# Single_Matrix.net
KiCad netlist of a schematic drawn in Altium Designer
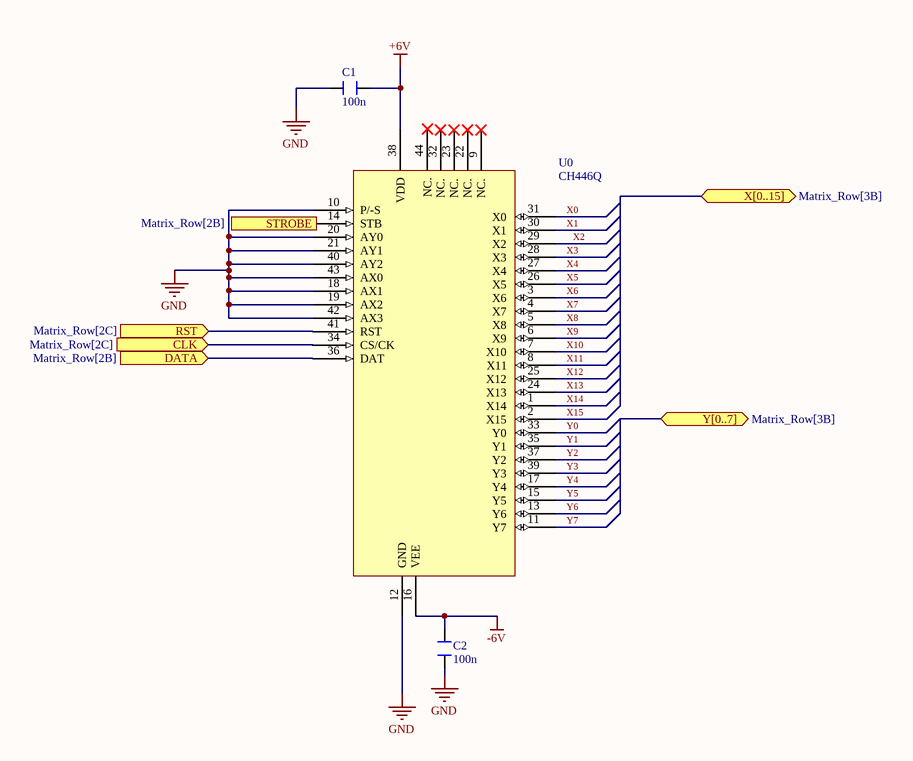
[diagram p0: Single_Matrix.SchDoc]

(export (version "E")
  (design (tool "Eeschema 10.0.6"))
  (components
    (comp (ref "C1")
      (value "100n")
      (footprint "micr_footprints:CL10B104KB8NNNC")
      (description "Capacitor SMD 0603 100n to VDD, VBAT, VDDA, VREF+, VDDUSB, NRST")
      (libsource (lib "unwired_schematic") (part "CL10B104KB8NNNC"))
    )
    (comp (ref "C2")
      (value "100n")
      (footprint "micr_footprints:CL10B104KB8NNNC")
      (description "Capacitor SMD 0603 100n to VDD, VBAT, VDDA, VREF+, VDDUSB, NRST")
      (libsource (lib "unwired_schematic") (part "CL10B104KB8NNNC"))
    )
    (comp (ref "U0")
      (value "CH446Q")
      (footprint "unwired_footprints:LQFP-44_CH446Q")
      (description "Analog Switch Array")
      (libsource (lib "unwired_schematic") (part "CH446Q"))
    )
  )
  (nets
    (net (code "1") (name "+6V") (class "Default")
      (node (ref "C1") (pin "8") (pintype "passive"))
      (node (ref "U0") (pin "38") (pinfunction "VDD_38") (pintype "power_in"))
    )
    (net (code "2") (name "-6V") (class "Default")
      (node (ref "C2") (pin "8") (pintype "passive"))
      (node (ref "U0") (pin "16") (pinfunction "VEE_16") (pintype "power_in"))
    )
    (net (code "3") (name "/CLK") (class "Default")
      (node (ref "U0") (pin "34") (pinfunction "CS/CK_34") (pintype "input"))
    )
    (net (code "4") (name "/DATA") (class "Default")
      (node (ref "U0") (pin "36") (pinfunction "DAT_36") (pintype "input"))
    )
    (net (code "5") (name "/RST") (class "Default")
      (node (ref "U0") (pin "41") (pinfunction "RST_41") (pintype "input"))
    )
    (net (code "7") (name "/X0") (class "Default")
      (node (ref "U0") (pin "31") (pinfunction "X0_31") (pintype "bidirectional"))
    )
    (net (code "8") (name "/X1") (class "Default")
      (node (ref "U0") (pin "30") (pinfunction "X1_30") (pintype "bidirectional"))
    )
    (net (code "9") (name "/X2") (class "Default")
      (node (ref "U0") (pin "29") (pinfunction "X2_29") (pintype "bidirectional"))
    )
    (net (code "10") (name "/X3") (class "Default")
      (node (ref "U0") (pin "28") (pinfunction "X3_28") (pintype "bidirectional"))
    )
    (net (code "11") (name "/X4") (class "Default")
      (node (ref "U0") (pin "27") (pinfunction "X4_27") (pintype "bidirectional"))
    )
    (net (code "12") (name "/X5") (class "Default")
      (node (ref "U0") (pin "26") (pinfunction "X5_26") (pintype "bidirectional"))
    )
    (net (code "13") (name "/X6") (class "Default")
      (node (ref "U0") (pin "3") (pinfunction "X6_3") (pintype "bidirectional"))
    )
    (net (code "14") (name "/X7") (class "Default")
      (node (ref "U0") (pin "4") (pinfunction "X7_4") (pintype "bidirectional"))
    )
    (net (code "15") (name "/X8") (class "Default")
      (node (ref "U0") (pin "5") (pinfunction "X8_5") (pintype "bidirectional"))
    )
    (net (code "16") (name "/X9") (class "Default")
      (node (ref "U0") (pin "6") (pinfunction "X9_6") (pintype "bidirectional"))
    )
    (net (code "17") (name "/X10") (class "Default")
      (node (ref "U0") (pin "7") (pinfunction "X10_7") (pintype "bidirectional"))
    )
    (net (code "18") (name "/X11") (class "Default")
      (node (ref "U0") (pin "8") (pinfunction "X11_8") (pintype "bidirectional"))
    )
    (net (code "19") (name "/X12") (class "Default")
      (node (ref "U0") (pin "25") (pinfunction "X12_25") (pintype "bidirectional"))
    )
    (net (code "20") (name "/X13") (class "Default")
      (node (ref "U0") (pin "24") (pinfunction "X13_24") (pintype "bidirectional"))
    )
    (net (code "21") (name "/X14") (class "Default")
      (node (ref "U0") (pin "1") (pinfunction "X14_1") (pintype "bidirectional"))
    )
    (net (code "24") (name "/Y0") (class "Default")
      (node (ref "U0") (pin "33") (pinfunction "Y0_33") (pintype "bidirectional"))
    )
    (net (code "25") (name "/Y1") (class "Default")
      (node (ref "U0") (pin "35") (pinfunction "Y1_35") (pintype "bidirectional"))
    )
    (net (code "26") (name "/Y2") (class "Default")
      (node (ref "U0") (pin "37") (pinfunction "Y2_37") (pintype "bidirectional"))
    )
    (net (code "27") (name "/Y3") (class "Default")
      (node (ref "U0") (pin "39") (pinfunction "Y3_39") (pintype "bidirectional"))
    )
    (net (code "28") (name "/Y4") (class "Default")
      (node (ref "U0") (pin "17") (pinfunction "Y4_17") (pintype "bidirectional"))
    )
    (net (code "29") (name "/Y5") (class "Default")
      (node (ref "U0") (pin "15") (pinfunction "Y5_15") (pintype "bidirectional"))
    )
    (net (code "30") (name "/Y6") (class "Default")
      (node (ref "U0") (pin "13") (pinfunction "Y6_13") (pintype "bidirectional"))
    )
    (net (code "31") (name "/Y7") (class "Default")
      (node (ref "U0") (pin "11") (pinfunction "Y7_11") (pintype "bidirectional"))
    )
    (net (code "33") (name "GND") (class "Default")
      (node (ref "C1") (pin "7") (pintype "passive"))
      (node (ref "C2") (pin "7") (pintype "passive"))
      (node (ref "U0") (pin "10") (pinfunction "P/-S_10") (pintype "input"))
      (node (ref "U0") (pin "12") (pinfunction "GND_12") (pintype "power_in"))
      (node (ref "U0") (pin "18") (pinfunction "AX1_18") (pintype "input"))
      (node (ref "U0") (pin "19") (pinfunction "AX2_19") (pintype "input"))
      (node (ref "U0") (pin "20") (pinfunction "AY0_20") (pintype "input"))
      (node (ref "U0") (pin "21") (pinfunction "AY1_21") (pintype "input"))
      (node (ref "U0") (pin "40") (pinfunction "AY2_40") (pintype "input"))
      (node (ref "U0") (pin "42") (pinfunction "AX3_42") (pintype "input"))
      (node (ref "U0") (pin "43") (pinfunction "AX0_43") (pintype "input"))
    )
    (net (code "34") (name "unconnected-(U0-NC.-Pad9)") (class "Default")
      (node (ref "U0") (pin "9") (pinfunction "NC._9") (pintype "passive+no_connect"))
    )
    (net (code "35") (name "unconnected-(U0-NC.-Pad22)") (class "Default")
      (node (ref "U0") (pin "22") (pinfunction "NC._22") (pintype "passive+no_connect"))
    )
    (net (code "36") (name "unconnected-(U0-NC.-Pad23)") (class "Default")
      (node (ref "U0") (pin "23") (pinfunction "NC._23") (pintype "passive+no_connect"))
    )
    (net (code "37") (name "unconnected-(U0-NC.-Pad32)") (class "Default")
      (node (ref "U0") (pin "32") (pinfunction "NC._32") (pintype "passive+no_connect"))
    )
    (net (code "38") (name "unconnected-(U0-NC.-Pad44)") (class "Default")
      (node (ref "U0") (pin "44") (pinfunction "NC._44") (pintype "passive+no_connect"))
    )
    (net (code "39") (name "unconnected-(U0-STB-Pad14)") (class "Default")
      (node (ref "U0") (pin "14") (pinfunction "STB_14") (pintype "input"))
    )
    (net (code "40") (name "unconnected-(U0-X15-Pad2)") (class "Default")
      (node (ref "U0") (pin "2") (pinfunction "X15_2") (pintype "bidirectional"))
    )
  )
)
